# Charger_PCB.net
KiCad netlist of a schematic drawn in EAGLE
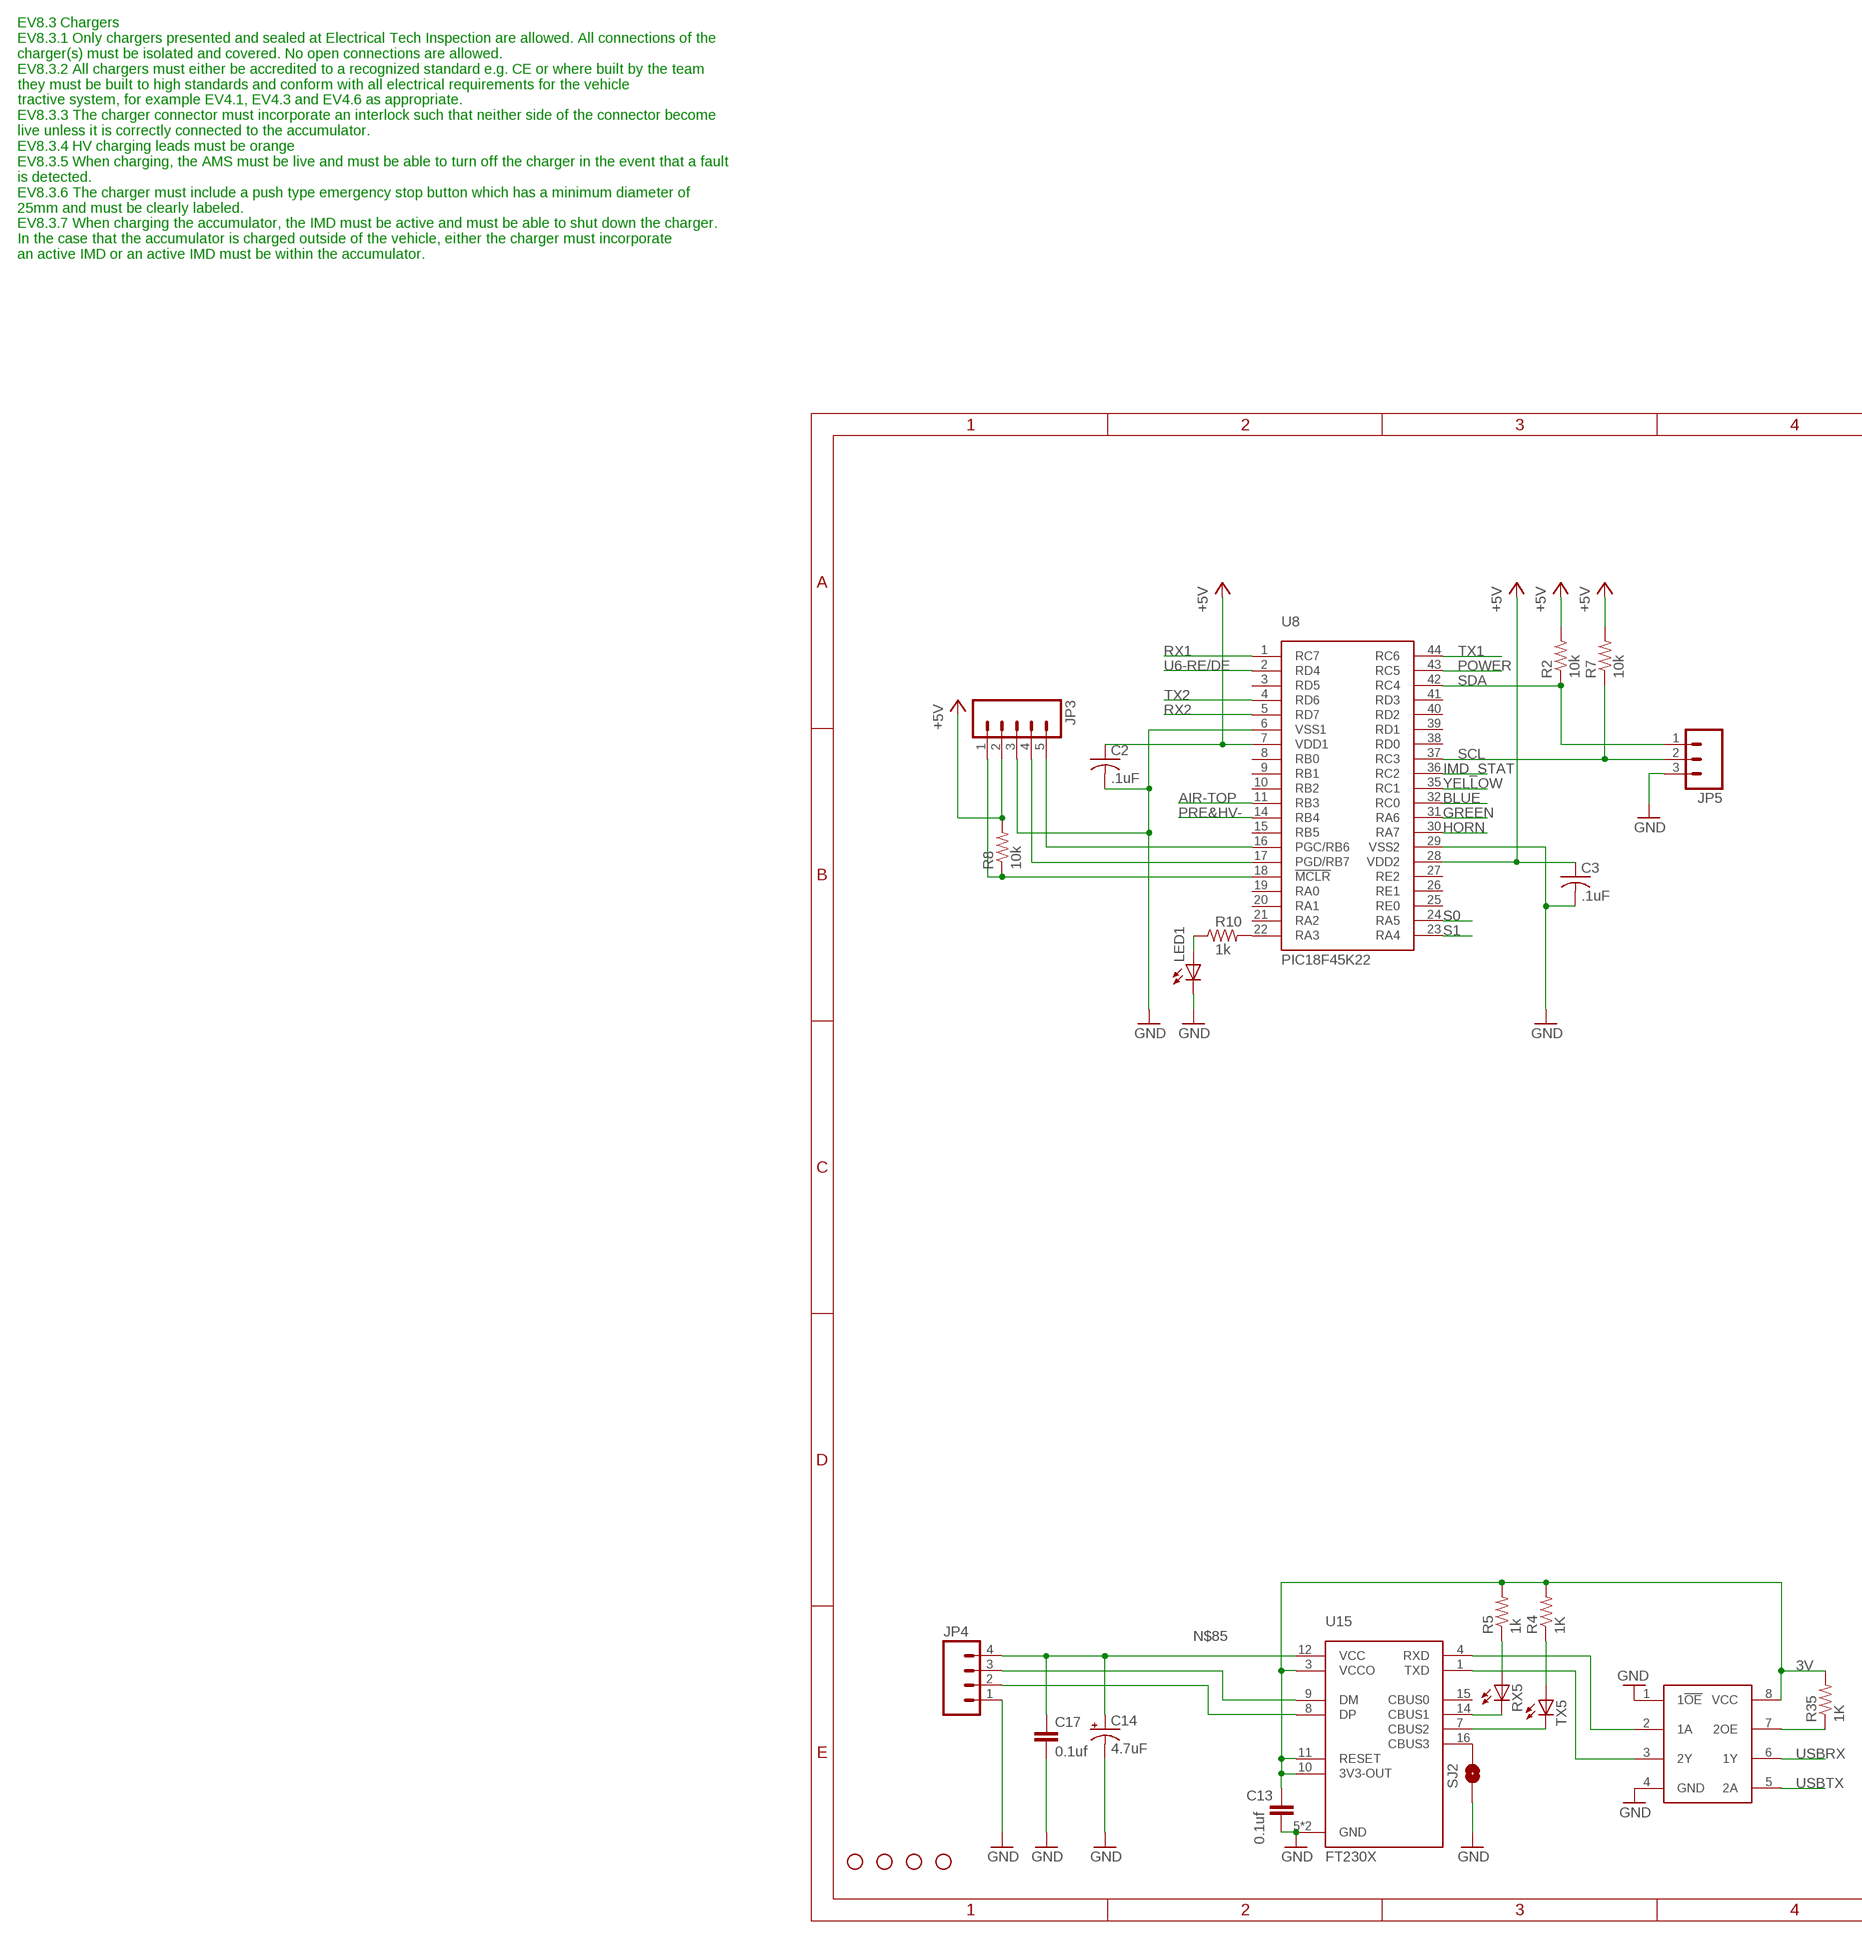
[diagram p0: schematic, sheet 1, part 1 of 2]
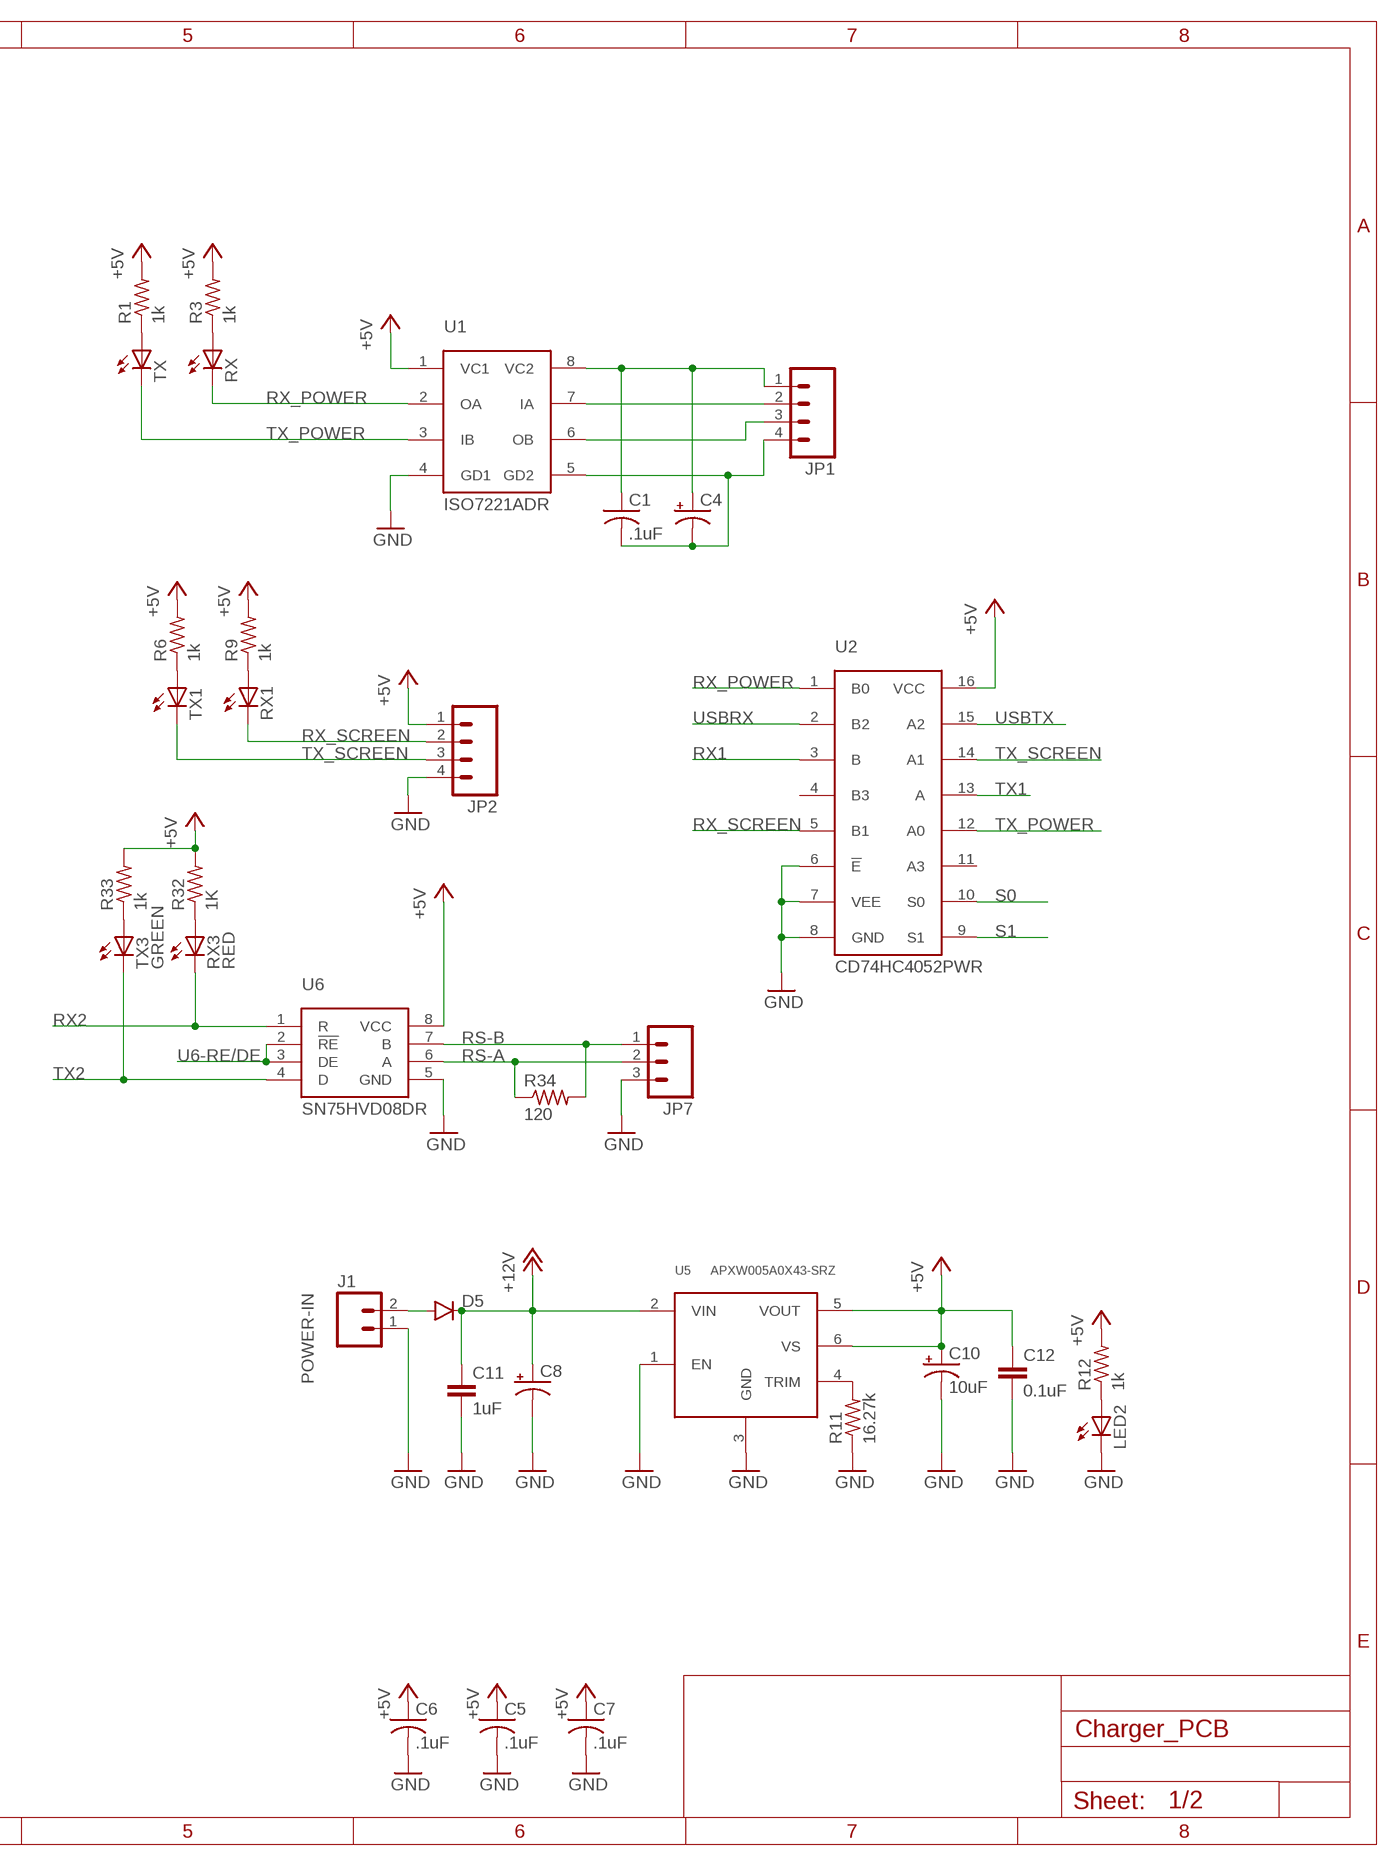
[diagram p1: schematic, sheet 1, part 2 of 2]
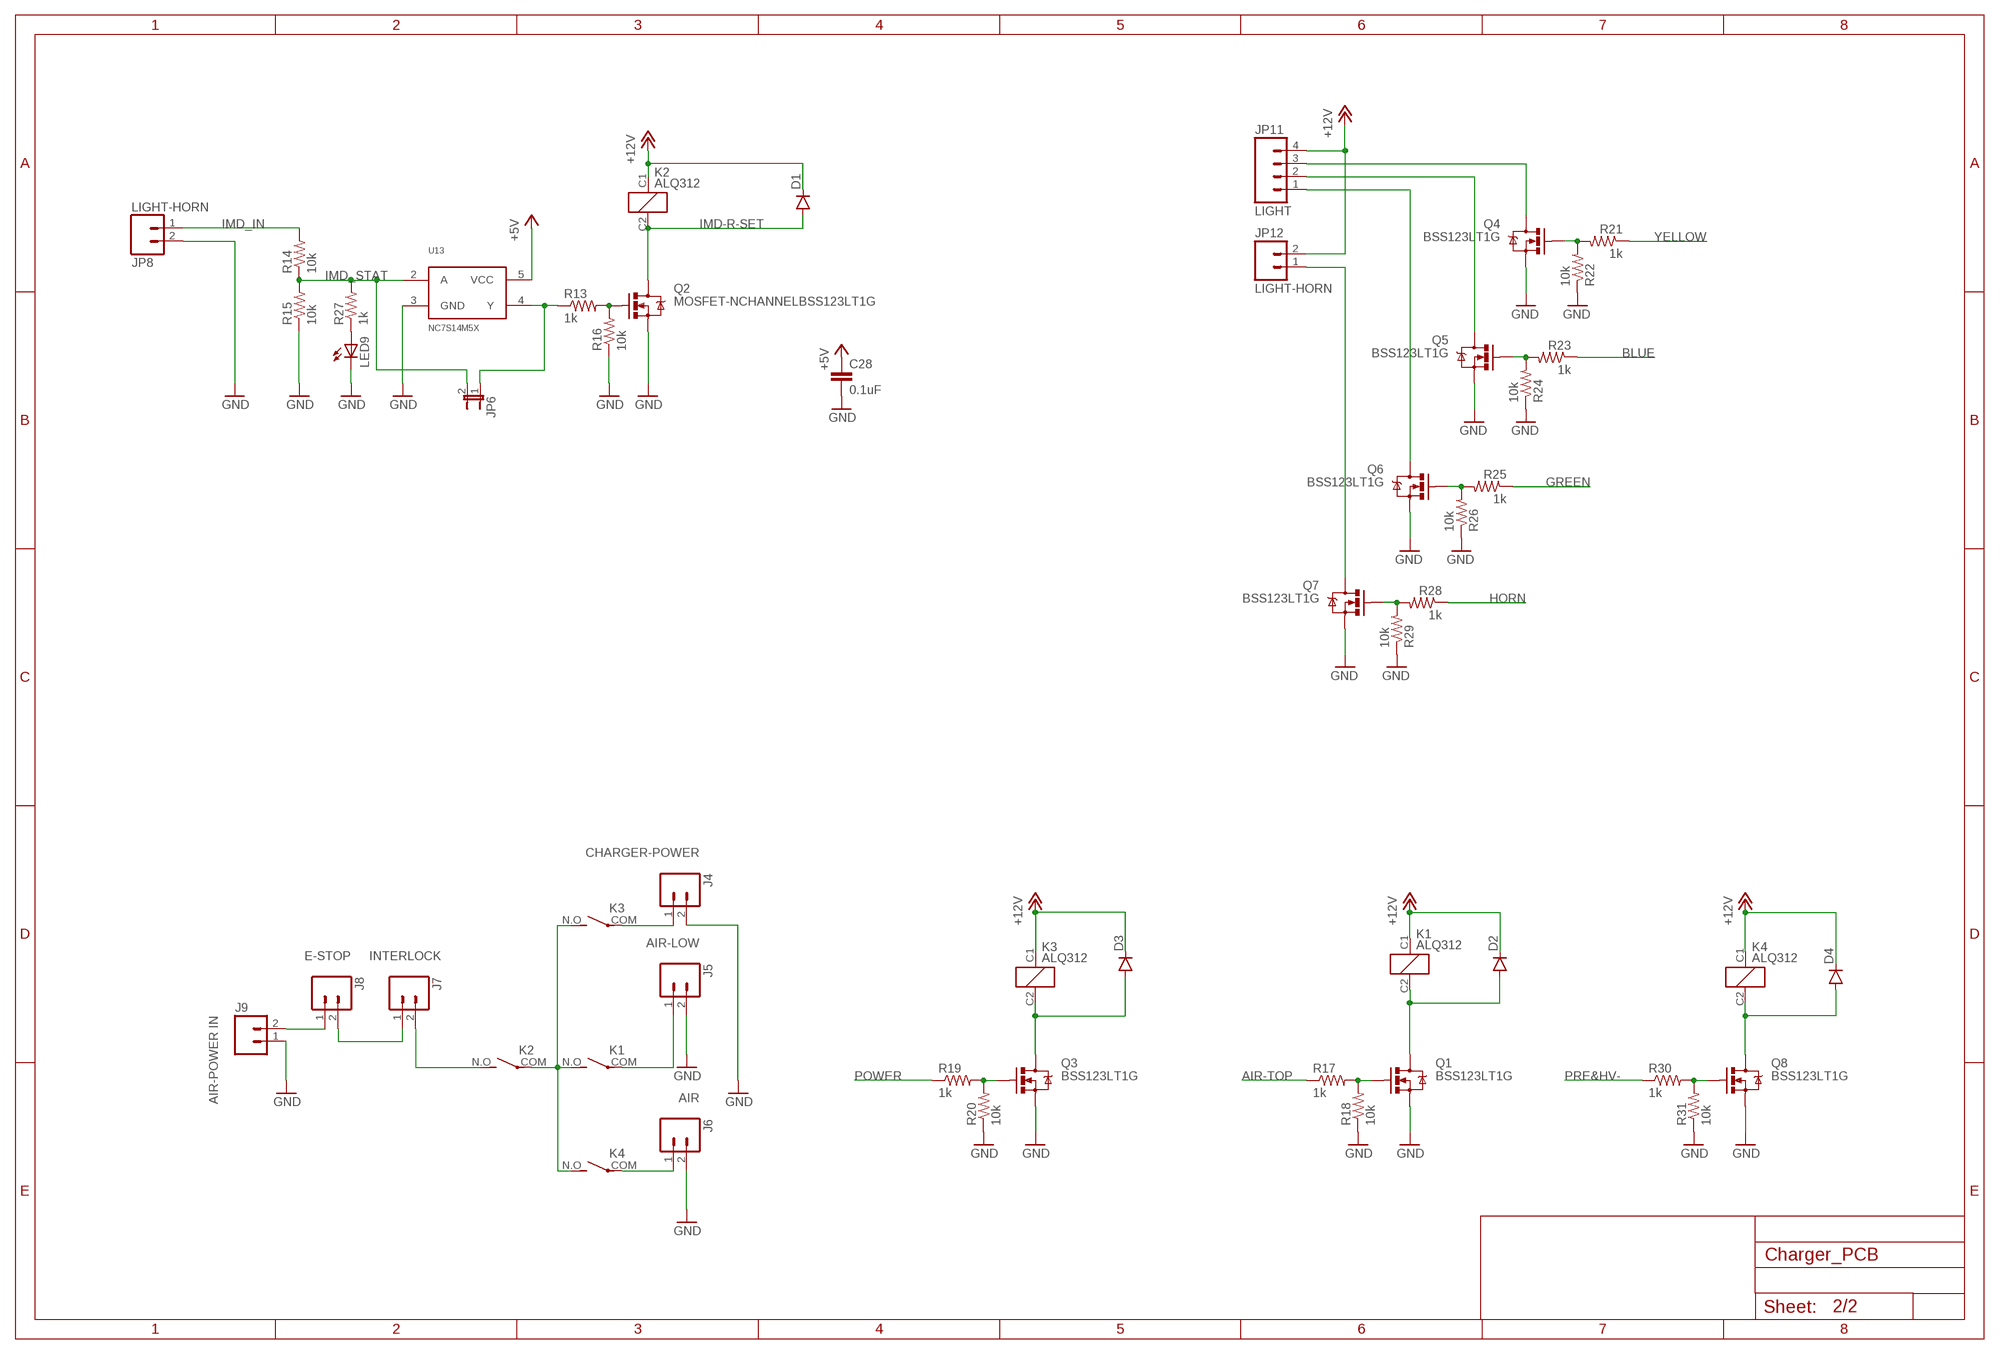
[diagram p2: schematic, sheet 2]

(export (version "E")
  (design (tool "Eeschema 10.0.6"))
  (components
    (comp (ref "C1")
      (value ".1uF")
      (footprint "eagle-import:C0805")
      (libsource (lib "eagle-import") (part "C-USC0805"))
    )
    (comp (ref "C2")
      (value ".1uF")
      (footprint "eagle-import:C0805")
      (libsource (lib "eagle-import") (part "C-USC0805"))
    )
    (comp (ref "C3")
      (value ".1uF")
      (footprint "eagle-import:C0805")
      (libsource (lib "eagle-import") (part "C-USC0805"))
    )
    (comp (ref "C4")
      (value "CAP_POL1206-KIT")
      (footprint "eagle-import:EIA3216-KIT")
      (libsource (lib "eagle-import") (part "SparkFun-Passives_CAP_POL1206-KIT"))
    )
    (comp (ref "C5")
      (value ".1uF")
      (footprint "eagle-import:C0805")
      (libsource (lib "eagle-import") (part "C-USC0805"))
    )
    (comp (ref "C6")
      (value ".1uF")
      (footprint "eagle-import:C0805")
      (libsource (lib "eagle-import") (part "C-USC0805"))
    )
    (comp (ref "C7")
      (value ".1uF")
      (footprint "eagle-import:C0805")
      (libsource (lib "eagle-import") (part "C-USC0805"))
    )
    (comp (ref "C8")
      (value "CAP_POLE")
      (footprint "eagle-import:PANASONIC_E")
      (libsource (lib "eagle-import") (part "SparkFun-Capacitors_CAP_POLE"))
    )
    (comp (ref "C10")
      (value "10uF")
      (footprint "eagle-import:EIA6032")
      (libsource (lib "eagle-import") (part "SparkFun-Capacitors_CAP_POL6032"))
    )
    (comp (ref "C11")
      (value "1uF")
      (footprint "eagle-import:1206")
      (libsource (lib "eagle-import") (part "SparkFun-Capacitors_CAP1206"))
    )
    (comp (ref "C12")
      (value "0.1uF")
      (footprint "eagle-import:0805")
      (libsource (lib "eagle-import") (part "SparkFun-Capacitors_CAP0805"))
    )
    (comp (ref "C13")
      (value "0.1uf")
      (footprint "eagle-import:0805")
      (libsource (lib "eagle-import") (part "CAP0805"))
    )
    (comp (ref "C14")
      (value "4.7uF")
      (footprint "eagle-import:EIA3216")
      (libsource (lib "eagle-import") (part "CAP_POL1206"))
    )
    (comp (ref "C17")
      (value "0.1uf")
      (footprint "eagle-import:0805")
      (libsource (lib "eagle-import") (part "CAP0805"))
    )
    (comp (ref "D5")
      (value "DIODEHV")
      (footprint "eagle-import:DIODE-HV")
      (libsource (lib "eagle-import") (part "DIODEHV"))
    )
    (comp (ref "J1")
      (value "POWER-IN")
      (footprint "eagle-import:M2")
      (libsource (lib "eagle-import") (part "EUROMAG-290DEG"))
    )
    (comp (ref "JP1")
      (value "M04POLAR_LOCK")
      (footprint "eagle-import:MOLEX-1X4_LOCK")
      (libsource (lib "eagle-import") (part "M04POLAR_LOCK"))
    )
    (comp (ref "JP2")
      (value "M04POLAR_LOCK")
      (footprint "eagle-import:MOLEX-1X4_LOCK")
      (libsource (lib "eagle-import") (part "M04POLAR_LOCK"))
    )
    (comp (ref "JP3")
      (value "M05LOCK_LONGPADS")
      (footprint "eagle-import:1X05_LOCK_LONGPADS")
      (libsource (lib "eagle-import") (part "M05LOCK_LONGPADS"))
    )
    (comp (ref "JP4")
      (value "M04POLAR_LOCK")
      (footprint "eagle-import:MOLEX-1X4_LOCK")
      (libsource (lib "eagle-import") (part "M04POLAR_LOCK"))
    )
    (comp (ref "JP5")
      (value "M03POLAR_LOCK")
      (footprint "eagle-import:MOLEX-1X3_LOCK")
      (libsource (lib "eagle-import") (part "M03POLAR_LOCK"))
    )
    (comp (ref "JP7")
      (value "M03POLAR_LOCK")
      (footprint "eagle-import:MOLEX-1X3_LOCK")
      (libsource (lib "eagle-import") (part "M03POLAR_LOCK"))
    )
    (comp (ref "LED1")
      (value "LEDCHIP-LED0805")
      (footprint "eagle-import:CHIP-LED0805")
      (libsource (lib "eagle-import") (part "LEDCHIP-LED0805"))
    )
    (comp (ref "LED2")
      (value "LEDCHIPLED_0805")
      (footprint "eagle-import:CHIPLED_0805")
      (libsource (lib "eagle-import") (part "LEDCHIPLED_0805"))
    )
    (comp (ref "R1")
      (value "1k")
      (footprint "eagle-import:R0805")
      (libsource (lib "eagle-import") (part "R-US_R0805"))
    )
    (comp (ref "R2")
      (value "10k")
      (footprint "eagle-import:R0805")
      (libsource (lib "eagle-import") (part "R-US_R0805"))
    )
    (comp (ref "R3")
      (value "1k")
      (footprint "eagle-import:R0805")
      (libsource (lib "eagle-import") (part "R-US_R0805"))
    )
    (comp (ref "R4")
      (value "1K")
      (footprint "eagle-import:R0805")
      (libsource (lib "eagle-import") (part "R-US_R0805"))
    )
    (comp (ref "R5")
      (value "1k")
      (footprint "eagle-import:R0805")
      (libsource (lib "eagle-import") (part "R-US_R0805"))
    )
    (comp (ref "R6")
      (value "1k")
      (footprint "eagle-import:R0805")
      (libsource (lib "eagle-import") (part "R-US_R0805"))
    )
    (comp (ref "R7")
      (value "10k")
      (footprint "eagle-import:R0805")
      (libsource (lib "eagle-import") (part "R-US_R0805"))
    )
    (comp (ref "R8")
      (value "10k")
      (footprint "eagle-import:0805")
      (libsource (lib "eagle-import") (part "RESISTOR0805-RES"))
    )
    (comp (ref "R9")
      (value "1k")
      (footprint "eagle-import:R0805")
      (libsource (lib "eagle-import") (part "R-US_R0805"))
    )
    (comp (ref "R10")
      (value "1k")
      (footprint "eagle-import:R0805")
      (libsource (lib "eagle-import") (part "R-US_R0805"))
    )
    (comp (ref "R11")
      (value "16.27k")
      (footprint "eagle-import:R0805")
      (libsource (lib "eagle-import") (part "R-US_R0805"))
    )
    (comp (ref "R12")
      (value "1k")
      (footprint "eagle-import:R0805")
      (libsource (lib "eagle-import") (part "R-US_R0805"))
    )
    (comp (ref "R32")
      (value "1K")
      (footprint "eagle-import:R0805")
      (libsource (lib "eagle-import") (part "R-US_R0805"))
    )
    (comp (ref "R33")
      (value "1k")
      (footprint "eagle-import:R0805")
      (libsource (lib "eagle-import") (part "R-US_R0805"))
    )
    (comp (ref "R34")
      (value "120")
      (footprint "eagle-import:R0805")
      (libsource (lib "eagle-import") (part "R-US_R0805"))
    )
    (comp (ref "R35")
      (value "1K")
      (footprint "eagle-import:R0805")
      (libsource (lib "eagle-import") (part "R-US_R0805"))
    )
    (comp (ref "RX")
      (value "LEDCHIPLED_0805")
      (footprint "eagle-import:CHIPLED_0805")
      (libsource (lib "eagle-import") (part "LEDCHIPLED_0805"))
    )
    (comp (ref "RX1")
      (value "LEDCHIPLED_0805")
      (footprint "eagle-import:CHIPLED_0805")
      (libsource (lib "eagle-import") (part "LEDCHIPLED_0805"))
    )
    (comp (ref "RX3")
      (value "RED")
      (footprint "eagle-import:CHIPLED_0805")
      (libsource (lib "eagle-import") (part "LEDCHIPLED_0805"))
    )
    (comp (ref "RX5")
      (value "LEDCHIPLED_0805")
      (footprint "eagle-import:CHIPLED_0805")
      (libsource (lib "eagle-import") (part "LEDCHIPLED_0805"))
    )
    (comp (ref "SJ2")
      (value "JUMPER-PAD-2-NOYES_SILK")
      (footprint "eagle-import:PAD-JUMPER-2-NO_YES_SILK")
      (libsource (lib "eagle-import") (part "JUMPER-PAD-2-NOYES_SILK"))
    )
    (comp (ref "STANDOFF1")
      (value "STAND-OFF")
      (footprint "eagle-import:STAND-OFF")
      (libsource (lib "eagle-import") (part "STAND-OFF"))
    )
    (comp (ref "STANDOFF2")
      (value "STAND-OFF")
      (footprint "eagle-import:STAND-OFF")
      (libsource (lib "eagle-import") (part "STAND-OFF"))
    )
    (comp (ref "STANDOFF3")
      (value "STAND-OFF")
      (footprint "eagle-import:STAND-OFF")
      (libsource (lib "eagle-import") (part "STAND-OFF"))
    )
    (comp (ref "STANDOFF4")
      (value "STAND-OFF")
      (footprint "eagle-import:STAND-OFF")
      (libsource (lib "eagle-import") (part "STAND-OFF"))
    )
    (comp (ref "TX")
      (value "LEDCHIPLED_0805")
      (footprint "eagle-import:CHIPLED_0805")
      (libsource (lib "eagle-import") (part "LEDCHIPLED_0805"))
    )
    (comp (ref "TX1")
      (value "LEDCHIPLED_0805")
      (footprint "eagle-import:CHIPLED_0805")
      (libsource (lib "eagle-import") (part "LEDCHIPLED_0805"))
    )
    (comp (ref "TX3")
      (value "GREEN")
      (footprint "eagle-import:CHIPLED_0805")
      (libsource (lib "eagle-import") (part "LEDCHIPLED_0805"))
    )
    (comp (ref "TX5")
      (value "LEDCHIPLED_0805")
      (footprint "eagle-import:CHIPLED_0805")
      (libsource (lib "eagle-import") (part "LEDCHIPLED_0805"))
    )
    (comp (ref "U1")
      (value "ISO7221ADR")
      (footprint "eagle-import:SO08")
      (libsource (lib "eagle-import") (part "ISO7221ADR"))
    )
    (comp (ref "U2")
      (value "CD74HC4052PWR")
      (footprint "eagle-import:TSSOP-16")
      (libsource (lib "eagle-import") (part "CD74HC4052PWR"))
    )
    (comp (ref "U4")
      (value "SN74LVC2G241DCTR")
      (footprint "eagle-import:VFSOP-8")
      (libsource (lib "eagle-import") (part "SN74LVC2G241DCTR"))
    )
    (comp (ref "U5")
      (value "APXW005A0X43-SRZ")
      (footprint "eagle-import:APXW005A0X43-SRZ")
      (libsource (lib "eagle-import") (part "APXW005A0X43-SRZ"))
    )
    (comp (ref "U6")
      (value "SN75HVD08DR")
      (footprint "eagle-import:SO-8")
      (libsource (lib "eagle-import") (part "SN75HVD08DR"))
    )
    (comp (ref "U8")
      (value "PIC18F45K22")
      (footprint "eagle-import:TQFP-44")
      (libsource (lib "eagle-import") (part "PIC18F45K22"))
    )
    (comp (ref "U15")
      (value "FT230X")
      (footprint "eagle-import:SSOP-16")
      (libsource (lib "eagle-import") (part "FT230X"))
    )
    (comp (ref "C28")
      (value "0.1uF")
      (footprint "eagle-import:0805")
      (libsource (lib "eagle-import") (part "SparkFun-Passives_CAP0805"))
    )
    (comp (ref "D1")
      (value "DIODEHV")
      (footprint "eagle-import:DIODE-HV")
      (libsource (lib "eagle-import") (part "DIODEHV"))
    )
    (comp (ref "D2")
      (value "DIODEHV")
      (footprint "eagle-import:DIODE-HV")
      (libsource (lib "eagle-import") (part "DIODEHV"))
    )
    (comp (ref "D3")
      (value "DIODEHV")
      (footprint "eagle-import:DIODE-HV")
      (libsource (lib "eagle-import") (part "DIODEHV"))
    )
    (comp (ref "D4")
      (value "DIODEHV")
      (footprint "eagle-import:DIODE-HV")
      (libsource (lib "eagle-import") (part "DIODEHV"))
    )
    (comp (ref "J4")
      (value "CHARGER-POWER")
      (footprint "eagle-import:M2")
      (libsource (lib "eagle-import") (part "EUROMAG-290DEG"))
    )
    (comp (ref "J5")
      (value "AIR-LOW")
      (footprint "eagle-import:M2")
      (libsource (lib "eagle-import") (part "EUROMAG-290DEG"))
    )
    (comp (ref "J6")
      (value "AIR")
      (footprint "eagle-import:M2")
      (libsource (lib "eagle-import") (part "EUROMAG-290DEG"))
    )
    (comp (ref "J7")
      (value "INTERLOCK")
      (footprint "eagle-import:M2")
      (libsource (lib "eagle-import") (part "EUROMAG-290DEG"))
    )
    (comp (ref "J8")
      (value "E-STOP")
      (footprint "eagle-import:M2")
      (libsource (lib "eagle-import") (part "EUROMAG-290DEG"))
    )
    (comp (ref "J9")
      (value "AIR-POWER IN")
      (footprint "eagle-import:M2")
      (libsource (lib "eagle-import") (part "EUROMAG-290DEG"))
    )
    (comp (ref "JP6")
      (value "JUMPER-2SMD-NO")
      (footprint "eagle-import:SJ_2S-NO")
      (libsource (lib "eagle-import") (part "JUMPER-2SMD-NO"))
    )
    (comp (ref "JP8")
      (value "LIGHT-HORN")
      (footprint "eagle-import:MOLEX-1X2_LOCK")
      (libsource (lib "eagle-import") (part "M02POLAR_LOCK"))
    )
    (comp (ref "JP11")
      (value "LIGHT")
      (footprint "eagle-import:MOLEX-1X4_LOCK")
      (libsource (lib "eagle-import") (part "M04POLAR_LOCK"))
    )
    (comp (ref "JP12")
      (value "LIGHT-HORN")
      (footprint "eagle-import:MOLEX-1X2_LOCK")
      (libsource (lib "eagle-import") (part "M02POLAR_LOCK"))
    )
    (comp (ref "K1")
      (value "ALQ312")
      (footprint "eagle-import:ALQ312")
      (libsource (lib "eagle-import") (part "FSAE Eletric (2)_ALQ312"))
    )
    (comp (ref "K2")
      (value "ALQ312")
      (footprint "eagle-import:ALQ312")
      (libsource (lib "eagle-import") (part "FSAE Eletric (2)_ALQ312"))
    )
    (comp (ref "K3")
      (value "ALQ312")
      (footprint "eagle-import:ALQ312")
      (libsource (lib "eagle-import") (part "FSAE Eletric (2)_ALQ312"))
    )
    (comp (ref "K4")
      (value "ALQ312")
      (footprint "eagle-import:ALQ312")
      (libsource (lib "eagle-import") (part "ALQ312"))
    )
    (comp (ref "LED9")
      (value "LEDCHIPLED_0805")
      (footprint "eagle-import:CHIPLED_0805")
      (libsource (lib "eagle-import") (part "LEDCHIPLED_0805"))
    )
    (comp (ref "Q1")
      (value "BSS123LT1G")
      (footprint "eagle-import:SOT23")
      (libsource (lib "eagle-import") (part "MOSFET-NCHANNELBSS123LT1G"))
    )
    (comp (ref "Q2")
      (value "MOSFET-NCHANNELBSS123LT1G")
      (footprint "eagle-import:SOT23")
      (libsource (lib "eagle-import") (part "MOSFET-NCHANNELBSS123LT1G"))
    )
    (comp (ref "Q3")
      (value "BSS123LT1G")
      (footprint "eagle-import:SOT23")
      (libsource (lib "eagle-import") (part "MOSFET-NCHANNELBSS123LT1G"))
    )
    (comp (ref "Q4")
      (value "BSS123LT1G")
      (footprint "eagle-import:SOT23")
      (libsource (lib "eagle-import") (part "MOSFET-NCHANNELBSS123LT1G"))
    )
    (comp (ref "Q5")
      (value "BSS123LT1G")
      (footprint "eagle-import:SOT23")
      (libsource (lib "eagle-import") (part "MOSFET-NCHANNELBSS123LT1G"))
    )
    (comp (ref "Q6")
      (value "BSS123LT1G")
      (footprint "eagle-import:SOT23")
      (libsource (lib "eagle-import") (part "MOSFET-NCHANNELBSS123LT1G"))
    )
    (comp (ref "Q7")
      (value "BSS123LT1G")
      (footprint "eagle-import:SOT23")
      (libsource (lib "eagle-import") (part "MOSFET-NCHANNELBSS123LT1G"))
    )
    (comp (ref "Q8")
      (value "BSS123LT1G")
      (footprint "eagle-import:SOT23")
      (libsource (lib "eagle-import") (part "MOSFET-NCHANNELBSS123LT1G"))
    )
    (comp (ref "R13")
      (value "1k")
      (footprint "eagle-import:0805")
      (libsource (lib "eagle-import") (part "RESISTOR0805-RES"))
    )
    (comp (ref "R14")
      (value "10k")
      (footprint "eagle-import:0805")
      (libsource (lib "eagle-import") (part "RESISTOR0805-RES"))
    )
    (comp (ref "R15")
      (value "10k")
      (footprint "eagle-import:0805")
      (libsource (lib "eagle-import") (part "RESISTOR0805-RES"))
    )
    (comp (ref "R16")
      (value "10k")
      (footprint "eagle-import:0805")
      (libsource (lib "eagle-import") (part "RESISTOR0805-RES"))
    )
    (comp (ref "R17")
      (value "1k")
      (footprint "eagle-import:0805")
      (libsource (lib "eagle-import") (part "RESISTOR0805-RES"))
    )
    (comp (ref "R18")
      (value "10k")
      (footprint "eagle-import:0805")
      (libsource (lib "eagle-import") (part "RESISTOR0805-RES"))
    )
    (comp (ref "R19")
      (value "1k")
      (footprint "eagle-import:0805")
      (libsource (lib "eagle-import") (part "RESISTOR0805-RES"))
    )
    (comp (ref "R20")
      (value "10k")
      (footprint "eagle-import:0805")
      (libsource (lib "eagle-import") (part "RESISTOR0805-RES"))
    )
    (comp (ref "R21")
      (value "1k")
      (footprint "eagle-import:0805")
      (libsource (lib "eagle-import") (part "RESISTOR0805-RES"))
    )
    (comp (ref "R22")
      (value "10k")
      (footprint "eagle-import:0805")
      (libsource (lib "eagle-import") (part "RESISTOR0805-RES"))
    )
    (comp (ref "R23")
      (value "1k")
      (footprint "eagle-import:0805")
      (libsource (lib "eagle-import") (part "RESISTOR0805-RES"))
    )
    (comp (ref "R24")
      (value "10k")
      (footprint "eagle-import:0805")
      (libsource (lib "eagle-import") (part "RESISTOR0805-RES"))
    )
    (comp (ref "R25")
      (value "1k")
      (footprint "eagle-import:0805")
      (libsource (lib "eagle-import") (part "RESISTOR0805-RES"))
    )
    (comp (ref "R26")
      (value "10k")
      (footprint "eagle-import:0805")
      (libsource (lib "eagle-import") (part "RESISTOR0805-RES"))
    )
    (comp (ref "R27")
      (value "1k")
      (footprint "eagle-import:0805")
      (libsource (lib "eagle-import") (part "RESISTOR0805-RES"))
    )
    (comp (ref "R28")
      (value "1k")
      (footprint "eagle-import:0805")
      (libsource (lib "eagle-import") (part "RESISTOR0805-RES"))
    )
    (comp (ref "R29")
      (value "10k")
      (footprint "eagle-import:0805")
      (libsource (lib "eagle-import") (part "RESISTOR0805-RES"))
    )
    (comp (ref "R30")
      (value "1k")
      (footprint "eagle-import:0805")
      (libsource (lib "eagle-import") (part "RESISTOR0805-RES"))
    )
    (comp (ref "R31")
      (value "10k")
      (footprint "eagle-import:0805")
      (libsource (lib "eagle-import") (part "RESISTOR0805-RES"))
    )
    (comp (ref "U13")
      (value "NC7S14M5X")
      (footprint "eagle-import:SOT23-5")
      (libsource (lib "eagle-import") (part "NC7S14M5X"))
    )
  )
  (nets
    (net (code "1") (name "+5V") (class "Default")
      (node (ref "C10") (pin "P$1") (pinfunction "+_P$1") (pintype "passive"))
      (node (ref "C12") (pin "1") (pinfunction "1_1") (pintype "passive"))
      (node (ref "C2") (pin "1") (pinfunction "1_1") (pintype "passive"))
      (node (ref "C28") (pin "1") (pinfunction "1_1") (pintype "passive"))
      (node (ref "C3") (pin "1") (pinfunction "1_1") (pintype "passive"))
      (node (ref "C5") (pin "1") (pinfunction "1_1") (pintype "passive"))
      (node (ref "C6") (pin "1") (pinfunction "1_1") (pintype "passive"))
      (node (ref "C7") (pin "1") (pinfunction "1_1") (pintype "passive"))
      (node (ref "JP2") (pin "1") (pinfunction "1_1") (pintype "passive"))
      (node (ref "JP3") (pin "2") (pinfunction "2_2") (pintype "passive"))
      (node (ref "R1") (pin "2") (pinfunction "2_2") (pintype "passive"))
      (node (ref "R12") (pin "2") (pinfunction "2_2") (pintype "passive"))
      (node (ref "R2") (pin "2") (pinfunction "2_2") (pintype "passive"))
      (node (ref "R3") (pin "2") (pinfunction "2_2") (pintype "passive"))
      (node (ref "R32") (pin "2") (pinfunction "2_2") (pintype "passive"))
      (node (ref "R33") (pin "2") (pinfunction "2_2") (pintype "passive"))
      (node (ref "R6") (pin "2") (pinfunction "2_2") (pintype "passive"))
      (node (ref "R7") (pin "2") (pinfunction "2_2") (pintype "passive"))
      (node (ref "R8") (pin "2") (pinfunction "2_2") (pintype "passive"))
      (node (ref "R9") (pin "2") (pinfunction "2_2") (pintype "passive"))
      (node (ref "U1") (pin "1") (pinfunction "VC1_1") (pintype "bidirectional"))
      (node (ref "U13") (pin "5") (pinfunction "VCC_5") (pintype "bidirectional"))
      (node (ref "U2") (pin "16") (pinfunction "VCC_16") (pintype "bidirectional"))
      (node (ref "U5") (pin "5") (pinfunction "VOUT_5") (pintype "bidirectional"))
      (node (ref "U5") (pin "6") (pinfunction "VS_6") (pintype "bidirectional"))
      (node (ref "U6") (pin "8") (pinfunction "VCC_8") (pintype "bidirectional"))
      (node (ref "U8") (pin "28") (pinfunction "VDD2_28") (pintype "bidirectional"))
      (node (ref "U8") (pin "7") (pinfunction "VDD1_7") (pintype "bidirectional"))
    )
    (net (code "2") (name "+12V") (class "Default")
      (node (ref "C11") (pin "1") (pinfunction "1_1") (pintype "passive"))
      (node (ref "C8") (pin "+") (pinfunction "+_+") (pintype "passive"))
      (node (ref "D1") (pin "C") (pinfunction "C_C") (pintype "passive"))
      (node (ref "D2") (pin "C") (pinfunction "C_C") (pintype "passive"))
      (node (ref "D3") (pin "C") (pinfunction "C_C") (pintype "passive"))
      (node (ref "D4") (pin "C") (pinfunction "C_C") (pintype "passive"))
      (node (ref "D5") (pin "C") (pinfunction "C_C") (pintype "passive"))
      (node (ref "JP11") (pin "4") (pinfunction "4_4") (pintype "passive"))
      (node (ref "JP12") (pin "2") (pinfunction "2_2") (pintype "passive"))
      (node (ref "K1") (pin "C1") (pinfunction "+_C1") (pintype "passive"))
      (node (ref "K2") (pin "C1") (pinfunction "+_C1") (pintype "passive"))
      (node (ref "K3") (pin "C1") (pinfunction "+_C1") (pintype "passive"))
      (node (ref "K4") (pin "C1") (pinfunction "+_C1") (pintype "passive"))
      (node (ref "U5") (pin "2") (pinfunction "VIN_2") (pintype "bidirectional"))
    )
    (net (code "3") (name "3V") (class "Default")
      (node (ref "C13") (pin "1") (pinfunction "1_1") (pintype "passive"))
      (node (ref "R35") (pin "2") (pinfunction "2_2") (pintype "passive"))
      (node (ref "R4") (pin "2") (pinfunction "2_2") (pintype "passive"))
      (node (ref "R5") (pin "2") (pinfunction "2_2") (pintype "passive"))
      (node (ref "U15") (pin "10") (pinfunction "3V3-OUT_10") (pintype "bidirectional"))
      (node (ref "U15") (pin "11") (pinfunction "RESET_11") (pintype "bidirectional"))
      (node (ref "U15") (pin "3") (pinfunction "VCCO_3") (pintype "bidirectional"))
      (node (ref "U4") (pin "8") (pinfunction "VCC_8") (pintype "bidirectional"))
    )
    (net (code "4") (name "AIR-TOP") (class "Default")
      (node (ref "R17") (pin "1") (pinfunction "1_1") (pintype "passive"))
      (node (ref "U8") (pin "11") (pinfunction "RB3_11") (pintype "bidirectional"))
    )
    (net (code "5") (name "BLUE") (class "Default")
      (node (ref "R23") (pin "1") (pinfunction "1_1") (pintype "passive"))
      (node (ref "U8") (pin "32") (pinfunction "RC0_32") (pintype "bidirectional"))
    )
    (net (code "6") (name "GND") (class "Default")
      (node (ref "C10") (pin "P$2") (pinfunction "-_P$2") (pintype "passive"))
      (node (ref "C11") (pin "2") (pinfunction "2_2") (pintype "passive"))
      (node (ref "C12") (pin "2") (pinfunction "2_2") (pintype "passive"))
      (node (ref "C13") (pin "2") (pinfunction "2_2") (pintype "passive"))
      (node (ref "C14") (pin "C") (pinfunction "-_C") (pintype "passive"))
      (node (ref "C17") (pin "2") (pinfunction "2_2") (pintype "passive"))
      (node (ref "C2") (pin "2") (pinfunction "2_2") (pintype "passive"))
      (node (ref "C28") (pin "2") (pinfunction "2_2") (pintype "passive"))
      (node (ref "C3") (pin "2") (pinfunction "2_2") (pintype "passive"))
      (node (ref "C5") (pin "2") (pinfunction "2_2") (pintype "passive"))
      (node (ref "C6") (pin "2") (pinfunction "2_2") (pintype "passive"))
      (node (ref "C7") (pin "2") (pinfunction "2_2") (pintype "passive"))
      (node (ref "C8") (pin "-") (pinfunction "-_-") (pintype "passive"))
      (node (ref "J1") (pin "1") (pinfunction "1_1") (pintype "passive"))
      (node (ref "J4") (pin "2") (pinfunction "2_2") (pintype "passive"))
      (node (ref "J5") (pin "2") (pinfunction "2_2") (pintype "passive"))
      (node (ref "J6") (pin "2") (pinfunction "2_2") (pintype "passive"))
      (node (ref "J9") (pin "1") (pinfunction "1_1") (pintype "passive"))
      (node (ref "JP2") (pin "4") (pinfunction "4_4") (pintype "passive"))
      (node (ref "JP3") (pin "3") (pinfunction "3_3") (pintype "passive"))
      (node (ref "JP4") (pin "1") (pinfunction "1_1") (pintype "passive"))
      (node (ref "JP5") (pin "3") (pinfunction "3_3") (pintype "passive"))
      (node (ref "JP7") (pin "3") (pinfunction "3_3") (pintype "passive"))
      (node (ref "JP8") (pin "2") (pinfunction "2_2") (pintype "passive"))
      (node (ref "LED1") (pin "C") (pinfunction "C_C") (pintype "passive"))
      (node (ref "LED2") (pin "C") (pinfunction "C_C") (pintype "passive"))
      (node (ref "LED9") (pin "C") (pinfunction "C_C") (pintype "passive"))
      (node (ref "Q1") (pin "2") (pinfunction "S_2") (pintype "passive"))
      (node (ref "Q2") (pin "2") (pinfunction "S_2") (pintype "passive"))
      (node (ref "Q3") (pin "2") (pinfunction "S_2") (pintype "passive"))
      (node (ref "Q4") (pin "2") (pinfunction "S_2") (pintype "passive"))
      (node (ref "Q5") (pin "2") (pinfunction "S_2") (pintype "passive"))
      (node (ref "Q6") (pin "2") (pinfunction "S_2") (pintype "passive"))
      (node (ref "Q7") (pin "2") (pinfunction "S_2") (pintype "passive"))
      (node (ref "Q8") (pin "2") (pinfunction "S_2") (pintype "passive"))
      (node (ref "R11") (pin "1") (pinfunction "1_1") (pintype "passive"))
      (node (ref "R15") (pin "1") (pinfunction "1_1") (pintype "passive"))
      (node (ref "R16") (pin "1") (pinfunction "1_1") (pintype "passive"))
      (node (ref "R18") (pin "1") (pinfunction "1_1") (pintype "passive"))
      (node (ref "R20") (pin "1") (pinfunction "1_1") (pintype "passive"))
      (node (ref "R22") (pin "1") (pinfunction "1_1") (pintype "passive"))
      (node (ref "R24") (pin "1") (pinfunction "1_1") (pintype "passive"))
      (node (ref "R26") (pin "1") (pinfunction "1_1") (pintype "passive"))
      (node (ref "R29") (pin "1") (pinfunction "1_1") (pintype "passive"))
      (node (ref "R31") (pin "1") (pinfunction "1_1") (pintype "passive"))
      (node (ref "SJ2") (pin "1") (pinfunction "1_1") (pintype "passive"))
      (node (ref "U1") (pin "4") (pinfunction "GD1_4") (pintype "bidirectional"))
      (node (ref "U13") (pin "3") (pinfunction "GND_3") (pintype "bidirectional"))
      (node (ref "U15") (pin "13") (pinfunction "GND_13") (pintype "bidirectional"))
      (node (ref "U15") (pin "5") (pinfunction "GND_5") (pintype "bidirectional"))
      (node (ref "U2") (pin "6") (pinfunction "~{E}_6") (pintype "bidirectional"))
      (node (ref "U2") (pin "7") (pinfunction "VEE_7") (pintype "bidirectional"))
      (node (ref "U2") (pin "8") (pinfunction "GND_8") (pintype "bidirectional"))
      (node (ref "U4") (pin "1") (pinfunction "1~{OE}_1") (pintype "bidirectional"))
      (node (ref "U4") (pin "4") (pinfunction "GND_4") (pintype "bidirectional"))
      (node (ref "U5") (pin "1") (pinfunction "EN_1") (pintype "bidirectional"))
      (node (ref "U5") (pin "3") (pinfunction "GND_3") (pintype "bidirectional"))
      (node (ref "U6") (pin "5") (pinfunction "GND_5") (pintype "bidirectional"))
      (node (ref "U8") (pin "29") (pinfunction "VSS2_29") (pintype "bidirectional"))
      (node (ref "U8") (pin "6") (pinfunction "VSS1_6") (pintype "bidirectional"))
    )
    (net (code "7") (name "GREEN") (class "Default")
      (node (ref "R25") (pin "1") (pinfunction "1_1") (pintype "passive"))
      (node (ref "U8") (pin "31") (pinfunction "RA6_31") (pintype "bidirectional"))
    )
    (net (code "8") (name "HORN") (class "Default")
      (node (ref "R28") (pin "1") (pinfunction "1_1") (pintype "passive"))
      (node (ref "U8") (pin "30") (pinfunction "RA7_30") (pintype "bidirectional"))
    )
    (net (code "9") (name "IMD-R-SET") (class "Default")
      (node (ref "D1") (pin "A") (pinfunction "A_A") (pintype "passive"))
      (node (ref "K2") (pin "C2") (pinfunction "-_C2") (pintype "passive"))
      (node (ref "Q2") (pin "3") (pinfunction "D_3") (pintype "passive"))
    )
    (net (code "10") (name "IMD_IN") (class "Default")
      (node (ref "JP8") (pin "1") (pinfunction "1_1") (pintype "passive"))
      (node (ref "R14") (pin "2") (pinfunction "2_2") (pintype "passive"))
    )
    (net (code "11") (name "IMD_STAT") (class "Default")
      (node (ref "JP6") (pin "2") (pinfunction "2_2") (pintype "passive"))
      (node (ref "R14") (pin "1") (pinfunction "1_1") (pintype "passive"))
      (node (ref "R15") (pin "2") (pinfunction "2_2") (pintype "passive"))
      (node (ref "R27") (pin "2") (pinfunction "2_2") (pintype "passive"))
      (node (ref "U13") (pin "2") (pinfunction "A_2") (pintype "bidirectional"))
      (node (ref "U8") (pin "36") (pinfunction "RC2_36") (pintype "bidirectional"))
    )
    (net (code "12") (name "N$85") (class "Default")
      (node (ref "C14") (pin "A") (pinfunction "+_A") (pintype "passive"))
      (node (ref "C17") (pin "1") (pinfunction "1_1") (pintype "passive"))
      (node (ref "JP4") (pin "4") (pinfunction "4_4") (pintype "passive"))
      (node (ref "U15") (pin "12") (pinfunction "VCC_12") (pintype "bidirectional"))
    )
    (net (code "13") (name "Net-(C4-+)") (class "Default")
      (node (ref "C1") (pin "1") (pinfunction "1_1") (pintype "passive"))
      (node (ref "C4") (pin "A") (pinfunction "+_A") (pintype "passive"))
      (node (ref "JP1") (pin "1") (pinfunction "1_1") (pintype "passive"))
      (node (ref "U1") (pin "8") (pinfunction "VC2_8") (pintype "bidirectional"))
    )
    (net (code "14") (name "Net-(C4--)") (class "Default")
      (node (ref "C1") (pin "2") (pinfunction "2_2") (pintype "passive"))
      (node (ref "C4") (pin "C") (pinfunction "-_C") (pintype "passive"))
      (node (ref "JP1") (pin "4") (pinfunction "4_4") (pintype "passive"))
      (node (ref "U1") (pin "5") (pinfunction "GD2_5") (pintype "bidirectional"))
    )
    (net (code "15") (name "Net-(D5-PadA)") (class "Default")
      (node (ref "D5") (pin "A") (pinfunction "A_A") (pintype "passive"))
      (node (ref "J1") (pin "2") (pinfunction "2_2") (pintype "passive"))
    )
    (net (code "16") (name "Net-(J7-Pad1)") (class "Default")
      (node (ref "J7") (pin "1") (pinfunction "1_1") (pintype "passive"))
      (node (ref "J8") (pin "2") (pinfunction "2_2") (pintype "passive"))
    )
    (net (code "17") (name "Net-(J8-Pad1)") (class "Default")
      (node (ref "J8") (pin "1") (pinfunction "1_1") (pintype "passive"))
      (node (ref "J9") (pin "2") (pinfunction "2_2") (pintype "passive"))
    )
    (net (code "18") (name "Net-(K1A--)") (class "Default")
      (node (ref "D2") (pin "A") (pinfunction "A_A") (pintype "passive"))
      (node (ref "K1") (pin "C2") (pinfunction "-_C2") (pintype "passive"))
      (node (ref "Q1") (pin "3") (pinfunction "D_3") (pintype "passive"))
    )
    (net (code "19") (name "Net-(K1B-P)") (class "Default")
      (node (ref "J5") (pin "1") (pinfunction "1_1") (pintype "passive"))
      (node (ref "K1") (pin "COM") (pinfunction "P_COM") (pintype "passive"))
    )
    (net (code "20") (name "Net-(K1B-S)") (class "Default")
      (node (ref "K1") (pin "N.O") (pinfunction "S_N.O") (pintype "passive"))
      (node (ref "K2") (pin "COM") (pinfunction "P_COM") (pintype "passive"))
      (node (ref "K3") (pin "N.O") (pinfunction "S_N.O") (pintype "passive"))
      (node (ref "K4") (pin "N.O") (pinfunction "S_N.O") (pintype "passive"))
    )
    (net (code "21") (name "Net-(K2B-S)") (class "Default")
      (node (ref "J7") (pin "2") (pinfunction "2_2") (pintype "passive"))
      (node (ref "K2") (pin "N.O") (pinfunction "S_N.O") (pintype "passive"))
    )
    (net (code "22") (name "Net-(K3A--)") (class "Default")
      (node (ref "D3") (pin "A") (pinfunction "A_A") (pintype "passive"))
      (node (ref "K3") (pin "C2") (pinfunction "-_C2") (pintype "passive"))
      (node (ref "Q3") (pin "3") (pinfunction "D_3") (pintype "passive"))
    )
    (net (code "23") (name "Net-(K3B-P)") (class "Default")
      (node (ref "J4") (pin "1") (pinfunction "1_1") (pintype "passive"))
      (node (ref "K3") (pin "COM") (pinfunction "P_COM") (pintype "passive"))
    )
    (net (code "24") (name "Net-(K4A--)") (class "Default")
      (node (ref "D4") (pin "A") (pinfunction "A_A") (pintype "passive"))
      (node (ref "K4") (pin "C2") (pinfunction "-_C2") (pintype "passive"))
      (node (ref "Q8") (pin "3") (pinfunction "D_3") (pintype "passive"))
    )
    (net (code "25") (name "Net-(K4B-P)") (class "Default")
      (node (ref "J6") (pin "1") (pinfunction "1_1") (pintype "passive"))
      (node (ref "K4") (pin "COM") (pinfunction "P_COM") (pintype "passive"))
    )
    (net (code "26") (name "Net-(LED1-PadA)") (class "Default")
      (node (ref "LED1") (pin "A") (pinfunction "A_A") (pintype "passive"))
      (node (ref "R10") (pin "1") (pinfunction "1_1") (pintype "passive"))
    )
    (net (code "27") (name "Net-(LED2-PadA)") (class "Default")
      (node (ref "LED2") (pin "A") (pinfunction "A_A") (pintype "passive"))
      (node (ref "R12") (pin "1") (pinfunction "1_1") (pintype "passive"))
    )
    (net (code "28") (name "Net-(LED9-PadA)") (class "Default")
      (node (ref "LED9") (pin "A") (pinfunction "A_A") (pintype "passive"))
      (node (ref "R27") (pin "1") (pinfunction "1_1") (pintype "passive"))
    )
    (net (code "29") (name "Net-(Q1-G)") (class "Default")
      (node (ref "Q1") (pin "1") (pinfunction "G_1") (pintype "passive"))
      (node (ref "R17") (pin "2") (pinfunction "2_2") (pintype "passive"))
      (node (ref "R18") (pin "2") (pinfunction "2_2") (pintype "passive"))
    )
    (net (code "30") (name "Net-(Q2-G)") (class "Default")
      (node (ref "Q2") (pin "1") (pinfunction "G_1") (pintype "passive"))
      (node (ref "R13") (pin "2") (pinfunction "2_2") (pintype "passive"))
      (node (ref "R16") (pin "2") (pinfunction "2_2") (pintype "passive"))
    )
    (net (code "31") (name "Net-(Q3-G)") (class "Default")
      (node (ref "Q3") (pin "1") (pinfunction "G_1") (pintype "passive"))
      (node (ref "R19") (pin "2") (pinfunction "2_2") (pintype "passive"))
      (node (ref "R20") (pin "2") (pinfunction "2_2") (pintype "passive"))
    )
    (net (code "32") (name "Net-(Q4-D)") (class "Default")
      (node (ref "JP11") (pin "3") (pinfunction "3_3") (pintype "passive"))
      (node (ref "Q4") (pin "3") (pinfunction "D_3") (pintype "passive"))
    )
    (net (code "33") (name "Net-(Q4-G)") (class "Default")
      (node (ref "Q4") (pin "1") (pinfunction "G_1") (pintype "passive"))
      (node (ref "R21") (pin "2") (pinfunction "2_2") (pintype "passive"))
      (node (ref "R22") (pin "2") (pinfunction "2_2") (pintype "passive"))
    )
    (net (code "34") (name "Net-(Q5-D)") (class "Default")
      (node (ref "JP11") (pin "2") (pinfunction "2_2") (pintype "passive"))
      (node (ref "Q5") (pin "3") (pinfunction "D_3") (pintype "passive"))
    )
    (net (code "35") (name "Net-(Q5-G)") (class "Default")
      (node (ref "Q5") (pin "1") (pinfunction "G_1") (pintype "passive"))
      (node (ref "R23") (pin "2") (pinfunction "2_2") (pintype "passive"))
      (node (ref "R24") (pin "2") (pinfunction "2_2") (pintype "passive"))
    )
    (net (code "36") (name "Net-(Q6-D)") (class "Default")
      (node (ref "JP11") (pin "1") (pinfunction "1_1") (pintype "passive"))
      (node (ref "Q6") (pin "3") (pinfunction "D_3") (pintype "passive"))
    )
    (net (code "37") (name "Net-(Q6-G)") (class "Default")
      (node (ref "Q6") (pin "1") (pinfunction "G_1") (pintype "passive"))
      (node (ref "R25") (pin "2") (pinfunction "2_2") (pintype "passive"))
      (node (ref "R26") (pin "2") (pinfunction "2_2") (pintype "passive"))
    )
    (net (code "38") (name "Net-(Q7-D)") (class "Default")
      (node (ref "JP12") (pin "1") (pinfunction "1_1") (pintype "passive"))
      (node (ref "Q7") (pin "3") (pinfunction "D_3") (pintype "passive"))
    )
    (net (code "39") (name "Net-(Q7-G)") (class "Default")
      (node (ref "Q7") (pin "1") (pinfunction "G_1") (pintype "passive"))
      (node (ref "R28") (pin "2") (pinfunction "2_2") (pintype "passive"))
      (node (ref "R29") (pin "2") (pinfunction "2_2") (pintype "passive"))
    )
    (net (code "40") (name "Net-(Q8-G)") (class "Default")
      (node (ref "Q8") (pin "1") (pinfunction "G_1") (pintype "passive"))
      (node (ref "R30") (pin "2") (pinfunction "2_2") (pintype "passive"))
      (node (ref "R31") (pin "2") (pinfunction "2_2") (pintype "passive"))
    )
    (net (code "41") (name "Net-(R1-Pad1)") (class "Default")
      (node (ref "R1") (pin "1") (pinfunction "1_1") (pintype "passive"))
      (node (ref "TX") (pin "A") (pinfunction "A_A") (pintype "passive"))
    )
    (net (code "42") (name "Net-(R3-Pad1)") (class "Default")
      (node (ref "R3") (pin "1") (pinfunction "1_1") (pintype "passive"))
      (node (ref "RX") (pin "A") (pinfunction "A_A") (pintype "passive"))
    )
    (net (code "43") (name "Net-(R4-Pad1)") (class "Default")
      (node (ref "R4") (pin "1") (pinfunction "1_1") (pintype "passive"))
      (node (ref "TX5") (pin "A") (pinfunction "A_A") (pintype "passive"))
    )
    (net (code "44") (name "Net-(R5-Pad1)") (class "Default")
      (node (ref "R5") (pin "1") (pinfunction "1_1") (pintype "passive"))
      (node (ref "RX5") (pin "A") (pinfunction "A_A") (pintype "passive"))
    )
    (net (code "45") (name "Net-(R6-Pad1)") (class "Default")
      (node (ref "R6") (pin "1") (pinfunction "1_1") (pintype "passive"))
      (node (ref "TX1") (pin "A") (pinfunction "A_A") (pintype "passive"))
    )
    (net (code "46") (name "Net-(R9-Pad1)") (class "Default")
      (node (ref "R9") (pin "1") (pinfunction "1_1") (pintype "passive"))
      (node (ref "RX1") (pin "A") (pinfunction "A_A") (pintype "passive"))
    )
    (net (code "47") (name "Net-(R32-Pad1)") (class "Default")
      (node (ref "R32") (pin "1") (pinfunction "1_1") (pintype "passive"))
      (node (ref "RX3") (pin "A") (pinfunction "A_A") (pintype "passive"))
    )
    (net (code "48") (name "Net-(R33-Pad1)") (class "Default")
      (node (ref "R33") (pin "1") (pinfunction "1_1") (pintype "passive"))
      (node (ref "TX3") (pin "A") (pinfunction "A_A") (pintype "passive"))
    )
    (net (code "49") (name "Net-(U1-IA)") (class "Default")
      (node (ref "JP1") (pin "2") (pinfunction "2_2") (pintype "passive"))
      (node (ref "U1") (pin "7") (pinfunction "IA_7") (pintype "bidirectional"))
    )
    (net (code "50") (name "Net-(U1-OB)") (class "Default")
      (node (ref "JP1") (pin "3") (pinfunction "3_3") (pintype "passive"))
      (node (ref "U1") (pin "6") (pinfunction "OB_6") (pintype "bidirectional"))
    )
    (net (code "51") (name "Net-(U4-2OE)") (class "Default")
      (node (ref "R35") (pin "1") (pinfunction "1_1") (pintype "passive"))
      (node (ref "U4") (pin "7") (pinfunction "2OE_7") (pintype "bidirectional"))
    )
    (net (code "52") (name "Net-(U5-TRIM)") (class "Default")
      (node (ref "R11") (pin "2") (pinfunction "2_2") (pintype "passive"))
      (node (ref "U5") (pin "4") (pinfunction "TRIM_4") (pintype "bidirectional"))
    )
    (net (code "53") (name "Net-(U8-PGC{slash}RB6)") (class "Default")
      (node (ref "JP3") (pin "5") (pinfunction "5_5") (pintype "passive"))
      (node (ref "U8") (pin "16") (pinfunction "PGC/RB6_16") (pintype "bidirectional"))
    )
    (net (code "54") (name "Net-(U8-PGD{slash}RB7)") (class "Default")
      (node (ref "JP3") (pin "4") (pinfunction "4_4") (pintype "passive"))
      (node (ref "U8") (pin "17") (pinfunction "PGD/RB7_17") (pintype "bidirectional"))
    )
    (net (code "55") (name "Net-(U8-RA3)") (class "Default")
      (node (ref "R10") (pin "2") (pinfunction "2_2") (pintype "passive"))
      (node (ref "U8") (pin "22") (pinfunction "RA3_22") (pintype "bidirectional"))
    )
    (net (code "56") (name "Net-(U8-~{MCLR})") (class "Default")
      (node (ref "JP3") (pin "1") (pinfunction "1_1") (pintype "passive"))
      (node (ref "R8") (pin "1") (pinfunction "1_1") (pintype "passive"))
      (node (ref "U8") (pin "18") (pinfunction "~{MCLR}_18") (pintype "bidirectional"))
    )
    (net (code "57") (name "Net-(U13-Y)") (class "Default")
      (node (ref "JP6") (pin "1") (pinfunction "1_1") (pintype "passive"))
      (node (ref "R13") (pin "1") (pinfunction "1_1") (pintype "passive"))
      (node (ref "U13") (pin "4") (pinfunction "Y_4") (pintype "bidirectional"))
    )
    (net (code "58") (name "Net-(U15-CBUS1)") (class "Default")
      (node (ref "RX5") (pin "C") (pinfunction "C_C") (pintype "passive"))
      (node (ref "U15") (pin "14") (pinfunction "CBUS1_14") (pintype "bidirectional"))
    )
    (net (code "59") (name "Net-(U15-CBUS2)") (class "Default")
      (node (ref "TX5") (pin "C") (pinfunction "C_C") (pintype "passive"))
      (node (ref "U15") (pin "7") (pinfunction "CBUS2_7") (pintype "bidirectional"))
    )
    (net (code "60") (name "Net-(U15-CBUS3)") (class "Default")
      (node (ref "SJ2") (pin "2") (pinfunction "2_2") (pintype "passive"))
      (node (ref "U15") (pin "16") (pinfunction "CBUS3_16") (pintype "bidirectional"))
    )
    (net (code "61") (name "Net-(U15-DM)") (class "Default")
      (node (ref "JP4") (pin "3") (pinfunction "3_3") (pintype "passive"))
      (node (ref "U15") (pin "9") (pinfunction "DM_9") (pintype "bidirectional"))
    )
    (net (code "62") (name "Net-(U15-DP)") (class "Default")
      (node (ref "JP4") (pin "2") (pinfunction "2_2") (pintype "passive"))
      (node (ref "U15") (pin "8") (pinfunction "DP_8") (pintype "bidirectional"))
    )
    (net (code "63") (name "Net-(U15-RXD)") (class "Default")
      (node (ref "U15") (pin "4") (pinfunction "RXD_4") (pintype "bidirectional"))
      (node (ref "U4") (pin "2") (pinfunction "1A_2") (pintype "bidirectional"))
    )
    (net (code "64") (name "Net-(U15-TXD)") (class "Default")
      (node (ref "U15") (pin "1") (pinfunction "TXD_1") (pintype "bidirectional"))
      (node (ref "U4") (pin "3") (pinfunction "2Y_3") (pintype "bidirectional"))
    )
    (net (code "65") (name "POWER") (class "Default")
      (node (ref "R19") (pin "1") (pinfunction "1_1") (pintype "passive"))
      (node (ref "U8") (pin "43") (pinfunction "RC5_43") (pintype "bidirectional"))
    )
    (net (code "66") (name "PRE&HV-") (class "Default")
      (node (ref "R30") (pin "1") (pinfunction "1_1") (pintype "passive"))
      (node (ref "U8") (pin "14") (pinfunction "RB4_14") (pintype "bidirectional"))
    )
    (net (code "67") (name "RS-A") (class "Default")
      (node (ref "JP7") (pin "2") (pinfunction "2_2") (pintype "passive"))
      (node (ref "R34") (pin "1") (pinfunction "1_1") (pintype "passive"))
      (node (ref "U6") (pin "6") (pinfunction "A_6") (pintype "bidirectional"))
    )
    (net (code "68") (name "RS-B") (class "Default")
      (node (ref "JP7") (pin "1") (pinfunction "1_1") (pintype "passive"))
      (node (ref "R34") (pin "2") (pinfunction "2_2") (pintype "passive"))
      (node (ref "U6") (pin "7") (pinfunction "B_7") (pintype "bidirectional"))
    )
    (net (code "69") (name "RX1") (class "Default")
      (node (ref "U2") (pin "3") (pinfunction "B_3") (pintype "bidirectional"))
      (node (ref "U8") (pin "1") (pinfunction "RC7_1") (pintype "bidirectional"))
    )
    (net (code "70") (name "RX2") (class "Default")
      (node (ref "RX3") (pin "C") (pinfunction "C_C") (pintype "passive"))
      (node (ref "U6") (pin "1") (pinfunction "R_1") (pintype "bidirectional"))
      (node (ref "U8") (pin "5") (pinfunction "RD7_5") (pintype "bidirectional"))
    )
    (net (code "71") (name "RX_POWER") (class "Default")
      (node (ref "RX") (pin "C") (pinfunction "C_C") (pintype "passive"))
      (node (ref "U1") (pin "2") (pinfunction "OA_2") (pintype "bidirectional"))
      (node (ref "U2") (pin "1") (pinfunction "B0_1") (pintype "bidirectional"))
    )
    (net (code "72") (name "RX_SCREEN") (class "Default")
      (node (ref "JP2") (pin "2") (pinfunction "2_2") (pintype "passive"))
      (node (ref "RX1") (pin "C") (pinfunction "C_C") (pintype "passive"))
      (node (ref "U2") (pin "5") (pinfunction "B1_5") (pintype "bidirectional"))
    )
    (net (code "73") (name "S0") (class "Default")
      (node (ref "U2") (pin "10") (pinfunction "S0_10") (pintype "bidirectional"))
      (node (ref "U8") (pin "24") (pinfunction "RA5_24") (pintype "bidirectional"))
    )
    (net (code "74") (name "S1") (class "Default")
      (node (ref "U2") (pin "9") (pinfunction "S1_9") (pintype "bidirectional"))
      (node (ref "U8") (pin "23") (pinfunction "RA4_23") (pintype "bidirectional"))
    )
    (net (code "75") (name "SCL") (class "Default")
      (node (ref "JP5") (pin "2") (pinfunction "2_2") (pintype "passive"))
      (node (ref "R7") (pin "1") (pinfunction "1_1") (pintype "passive"))
      (node (ref "U8") (pin "37") (pinfunction "RC3_37") (pintype "bidirectional"))
    )
    (net (code "76") (name "SDA") (class "Default")
      (node (ref "JP5") (pin "1") (pinfunction "1_1") (pintype "passive"))
      (node (ref "R2") (pin "1") (pinfunction "1_1") (pintype "passive"))
      (node (ref "U8") (pin "42") (pinfunction "RC4_42") (pintype "bidirectional"))
    )
    (net (code "77") (name "TX1") (class "Default")
      (node (ref "U2") (pin "13") (pinfunction "A_13") (pintype "bidirectional"))
      (node (ref "U8") (pin "44") (pinfunction "RC6_44") (pintype "bidirectional"))
    )
    (net (code "78") (name "TX2") (class "Default")
      (node (ref "TX3") (pin "C") (pinfunction "C_C") (pintype "passive"))
      (node (ref "U6") (pin "4") (pinfunction "D_4") (pintype "bidirectional"))
      (node (ref "U8") (pin "4") (pinfunction "RD6_4") (pintype "bidirectional"))
    )
    (net (code "79") (name "TX_POWER") (class "Default")
      (node (ref "TX") (pin "C") (pinfunction "C_C") (pintype "passive"))
      (node (ref "U1") (pin "3") (pinfunction "IB_3") (pintype "bidirectional"))
      (node (ref "U2") (pin "12") (pinfunction "A0_12") (pintype "bidirectional"))
    )
    (net (code "80") (name "TX_SCREEN") (class "Default")
      (node (ref "JP2") (pin "3") (pinfunction "3_3") (pintype "passive"))
      (node (ref "TX1") (pin "C") (pinfunction "C_C") (pintype "passive"))
      (node (ref "U2") (pin "14") (pinfunction "A1_14") (pintype "bidirectional"))
    )
    (net (code "81") (name "U6-RE{slash}DE") (class "Default")
      (node (ref "U6") (pin "2") (pinfunction "~{RE}_2") (pintype "bidirectional"))
      (node (ref "U6") (pin "3") (pinfunction "DE_3") (pintype "bidirectional"))
      (node (ref "U8") (pin "2") (pinfunction "RD4_2") (pintype "bidirectional"))
    )
    (net (code "82") (name "USBRX") (class "Default")
      (node (ref "U2") (pin "2") (pinfunction "B2_2") (pintype "bidirectional"))
      (node (ref "U4") (pin "6") (pinfunction "1Y_6") (pintype "bidirectional"))
    )
    (net (code "83") (name "USBTX") (class "Default")
      (node (ref "U2") (pin "15") (pinfunction "A2_15") (pintype "bidirectional"))
      (node (ref "U4") (pin "5") (pinfunction "2A_5") (pintype "bidirectional"))
    )
    (net (code "84") (name "YELLOW") (class "Default")
      (node (ref "R21") (pin "1") (pinfunction "1_1") (pintype "passive"))
      (node (ref "U8") (pin "35") (pinfunction "RC1_35") (pintype "bidirectional"))
    )
    (net (code "85") (name "unconnected-(U2-A3-Pad11)") (class "Default")
      (node (ref "U2") (pin "11") (pinfunction "A3_11") (pintype "bidirectional"))
    )
    (net (code "86") (name "unconnected-(U2-B3-Pad4)") (class "Default")
      (node (ref "U2") (pin "4") (pinfunction "B3_4") (pintype "bidirectional"))
    )
    (net (code "87") (name "unconnected-(U8-RA0-Pad19)") (class "Default")
      (node (ref "U8") (pin "19") (pinfunction "RA0_19") (pintype "bidirectional"))
    )
    (net (code "88") (name "unconnected-(U8-RA1-Pad20)") (class "Default")
      (node (ref "U8") (pin "20") (pinfunction "RA1_20") (pintype "bidirectional"))
    )
    (net (code "89") (name "unconnected-(U8-RA2-Pad21)") (class "Default")
      (node (ref "U8") (pin "21") (pinfunction "RA2_21") (pintype "bidirectional"))
    )
    (net (code "90") (name "unconnected-(U8-RB0-Pad8)") (class "Default")
      (node (ref "U8") (pin "8") (pinfunction "RB0_8") (pintype "bidirectional"))
    )
    (net (code "91") (name "unconnected-(U8-RB1-Pad9)") (class "Default")
      (node (ref "U8") (pin "9") (pinfunction "RB1_9") (pintype "bidirectional"))
    )
    (net (code "92") (name "unconnected-(U8-RB2-Pad10)") (class "Default")
      (node (ref "U8") (pin "10") (pinfunction "RB2_10") (pintype "bidirectional"))
    )
    (net (code "93") (name "unconnected-(U8-RB5-Pad15)") (class "Default")
      (node (ref "U8") (pin "15") (pinfunction "RB5_15") (pintype "bidirectional"))
    )
    (net (code "94") (name "unconnected-(U8-RD0-Pad38)") (class "Default")
      (node (ref "U8") (pin "38") (pinfunction "RD0_38") (pintype "bidirectional"))
    )
    (net (code "95") (name "unconnected-(U8-RD1-Pad39)") (class "Default")
      (node (ref "U8") (pin "39") (pinfunction "RD1_39") (pintype "bidirectional"))
    )
    (net (code "96") (name "unconnected-(U8-RD2-Pad40)") (class "Default")
      (node (ref "U8") (pin "40") (pinfunction "RD2_40") (pintype "bidirectional"))
    )
    (net (code "97") (name "unconnected-(U8-RD3-Pad41)") (class "Default")
      (node (ref "U8") (pin "41") (pinfunction "RD3_41") (pintype "bidirectional"))
    )
    (net (code "98") (name "unconnected-(U8-RD5-Pad3)") (class "Default")
      (node (ref "U8") (pin "3") (pinfunction "RD5_3") (pintype "bidirectional"))
    )
    (net (code "99") (name "unconnected-(U8-RE0-Pad25)") (class "Default")
      (node (ref "U8") (pin "25") (pinfunction "RE0_25") (pintype "bidirectional"))
    )
    (net (code "100") (name "unconnected-(U8-RE1-Pad26)") (class "Default")
      (node (ref "U8") (pin "26") (pinfunction "RE1_26") (pintype "bidirectional"))
    )
    (net (code "101") (name "unconnected-(U8-RE2-Pad27)") (class "Default")
      (node (ref "U8") (pin "27") (pinfunction "RE2_27") (pintype "bidirectional"))
    )
    (net (code "102") (name "unconnected-(U15-CBUS0-Pad15)") (class "Default")
      (node (ref "U15") (pin "15") (pinfunction "CBUS0_15") (pintype "bidirectional"))
    )
  )
)
